# untitled.net
KiCad netlist of a schematic drawn in EAGLE
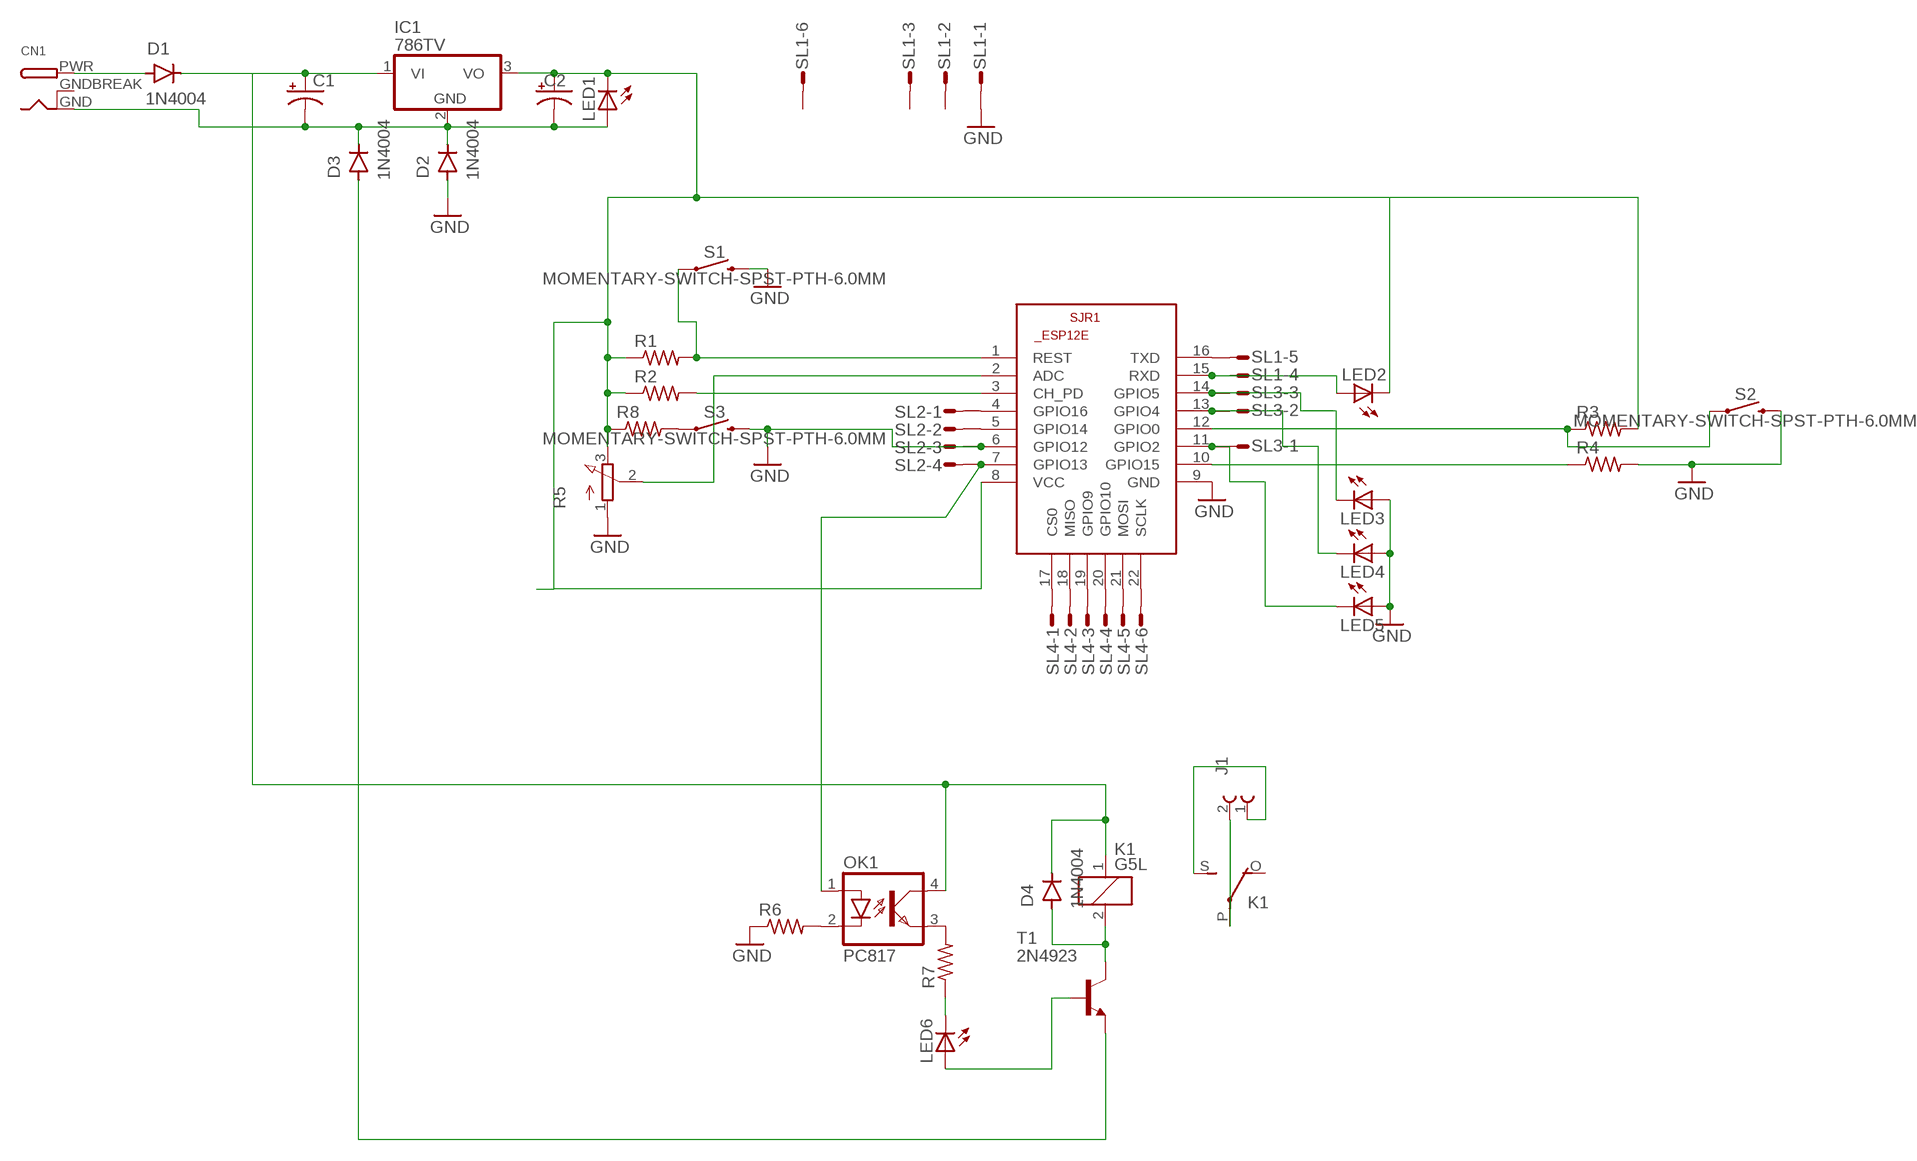
[diagram p0: schematic, sheet 1]

(export (version "E")
  (design (tool "Eeschema 10.0.6"))
  (components
    (comp (ref "C1")
      (value "CAPACITOR-PE3.5-8")
      (footprint "eagle-import:E3,5-8")
      (libsource (lib "eagle-import") (part "CAPACITOR-PE3.5-8"))
    )
    (comp (ref "C2")
      (value "CAPACITOR-PE3.5-8")
      (footprint "eagle-import:E3,5-8")
      (libsource (lib "eagle-import") (part "CAPACITOR-PE3.5-8"))
    )
    (comp (ref "CN1")
      (value "DCBARRELPTH")
      (footprint "eagle-import:DCJACK_2MM_PTH")
      (libsource (lib "eagle-import") (part "DCBARRELPTH"))
    )
    (comp (ref "D1")
      (value "1N4004")
      (footprint "eagle-import:DO-41")
      (fields
        (field (name "DIGIKEY_PART_NUMBER") "1N4004MSCT-ND")
        (field (name "MANUFACTURER") "Micro Commercial Co")
        (field (name "CREATED_BY") "PCBLayout.com")
      )
      (libsource (lib "eagle-import") (part "1N4004"))
    )
    (comp (ref "D2")
      (value "1N4004")
      (footprint "eagle-import:DO-41")
      (fields
        (field (name "DIGIKEY_PART_NUMBER") "1N4004MSCT-ND")
        (field (name "MANUFACTURER") "Micro Commercial Co")
        (field (name "CREATED_BY") "PCBLayout.com")
      )
      (libsource (lib "eagle-import") (part "1N4004"))
    )
    (comp (ref "D3")
      (value "1N4004")
      (footprint "eagle-import:DO-41")
      (fields
        (field (name "DIGIKEY_PART_NUMBER") "1N4004MSCT-ND")
        (field (name "MANUFACTURER") "Micro Commercial Co")
        (field (name "CREATED_BY") "PCBLayout.com")
      )
      (libsource (lib "eagle-import") (part "1N4004"))
    )
    (comp (ref "D4")
      (value "1N4004")
      (footprint "eagle-import:DO-41")
      (fields
        (field (name "DIGIKEY_PART_NUMBER") "1N4004MSCT-ND")
        (field (name "MANUFACTURER") "Micro Commercial Co")
        (field (name "CREATED_BY") "PCBLayout.com")
      )
      (libsource (lib "eagle-import") (part "1N4004"))
    )
    (comp (ref "IC1")
      (value "786TV")
      (footprint "eagle-import:TO220V")
      (libsource (lib "eagle-import") (part "78TV6"))
    )
    (comp (ref "J1")
      (value "691370710002B")
      (footprint "eagle-import:691370710002B")
      (libsource (lib "eagle-import") (part "691370710002B"))
    )
    (comp (ref "K1")
      (value "G5L")
      (footprint "eagle-import:G5LE")
      (libsource (lib "eagle-import") (part "G5L"))
    )
    (comp (ref "LED1")
      (value "LED5MM")
      (footprint "eagle-import:LED5MM")
      (libsource (lib "eagle-import") (part "LED5MM"))
    )
    (comp (ref "LED2")
      (value "LED5MM")
      (footprint "eagle-import:LED5MM")
      (libsource (lib "eagle-import") (part "LED5MM"))
    )
    (comp (ref "LED3")
      (value "LED5MM")
      (footprint "eagle-import:LED5MM")
      (libsource (lib "eagle-import") (part "LED5MM"))
    )
    (comp (ref "LED4")
      (value "LED5MM")
      (footprint "eagle-import:LED5MM")
      (libsource (lib "eagle-import") (part "LED5MM"))
    )
    (comp (ref "LED5")
      (value "LED5MM")
      (footprint "eagle-import:LED5MM")
      (libsource (lib "eagle-import") (part "LED5MM"))
    )
    (comp (ref "LED6")
      (value "LED5MM")
      (footprint "eagle-import:LED5MM")
      (libsource (lib "eagle-import") (part "LED5MM"))
    )
    (comp (ref "OK1")
      (value "PC817")
      (footprint "eagle-import:DIL04")
      (fields (field (name "MPN") "PC817X4J000F"))
      (libsource (lib "eagle-import") (part "PC817"))
    )
    (comp (ref "R1")
      (value "R-US_0309/10")
      (footprint "eagle-import:0309_10")
      (libsource (lib "eagle-import") (part "R-US_0309/10"))
    )
    (comp (ref "R2")
      (value "R-US_0309/10")
      (footprint "eagle-import:0309_10")
      (libsource (lib "eagle-import") (part "R-US_0309/10"))
    )
    (comp (ref "R3")
      (value "R-US_0309/10")
      (footprint "eagle-import:0309_10")
      (libsource (lib "eagle-import") (part "R-US_0309/10"))
    )
    (comp (ref "R4")
      (value "R-US_0309/10")
      (footprint "eagle-import:0309_10")
      (libsource (lib "eagle-import") (part "R-US_0309/10"))
    )
    (comp (ref "R5")
      (value "3RP/1610N")
      (footprint "eagle-import:3RP_1610N")
      (libsource (lib "eagle-import") (part "3RP/1610N"))
    )
    (comp (ref "R6")
      (value "R-US_0309/10")
      (footprint "eagle-import:0309_10")
      (libsource (lib "eagle-import") (part "R-US_0309/10"))
    )
    (comp (ref "R7")
      (value "R-US_0309/10")
      (footprint "eagle-import:0309_10")
      (libsource (lib "eagle-import") (part "R-US_0309/10"))
    )
    (comp (ref "R8")
      (value "R-US_0309/10")
      (footprint "eagle-import:0309_10")
      (libsource (lib "eagle-import") (part "R-US_0309/10"))
    )
    (comp (ref "S1")
      (value "MOMENTARY-SWITCH-SPST-PTH-6.0MM")
      (footprint "eagle-import:TACTILE_SWITCH_PTH_6.0MM")
      (libsource (lib "eagle-import") (part "MOMENTARY-SWITCH-SPST-PTH-6.0MM"))
    )
    (comp (ref "S2")
      (value "MOMENTARY-SWITCH-SPST-PTH-6.0MM")
      (footprint "eagle-import:TACTILE_SWITCH_PTH_6.0MM")
      (libsource (lib "eagle-import") (part "MOMENTARY-SWITCH-SPST-PTH-6.0MM"))
    )
    (comp (ref "S3")
      (value "MOMENTARY-SWITCH-SPST-PTH-6.0MM")
      (footprint "eagle-import:TACTILE_SWITCH_PTH_6.0MM")
      (libsource (lib "eagle-import") (part "MOMENTARY-SWITCH-SPST-PTH-6.0MM"))
    )
    (comp (ref "SJR1")
      (value "ESP8266-12EESP12E")
      (footprint "eagle-import:ESP8266-ESP12E")
      (libsource (lib "eagle-import") (part "ESP8266-12EESP12E"))
    )
    (comp (ref "SL1")
      (value "M06S")
      (footprint "eagle-import:06P")
      (libsource (lib "eagle-import") (part "M06S"))
    )
    (comp (ref "SL2")
      (value "M04S")
      (footprint "eagle-import:04P")
      (libsource (lib "eagle-import") (part "M04S"))
    )
    (comp (ref "SL3")
      (value "M03S")
      (footprint "eagle-import:03P")
      (libsource (lib "eagle-import") (part "M03S"))
    )
    (comp (ref "SL4")
      (value "M06S")
      (footprint "eagle-import:06P")
      (libsource (lib "eagle-import") (part "M06S"))
    )
    (comp (ref "T1")
      (value "2N4923")
      (footprint "eagle-import:TO126")
      (libsource (lib "eagle-import") (part "2N4923"))
    )
  )
  (nets
    (net (code "1") (name "/GNDBREAK") (class "Default")
      (node (ref "CN1") (pin "GNDBREAK") (pinfunction "GNDBREAK_GNDBREAK") (pintype "power_in"))
    )
    (net (code "2") (name "GND") (class "Default")
      (node (ref "D2") (pin "A") (pinfunction "A_A") (pintype "passive"))
      (node (ref "LED3") (pin "A") (pinfunction "A_A") (pintype "passive"))
      (node (ref "LED4") (pin "A") (pinfunction "A_A") (pintype "passive"))
      (node (ref "LED5") (pin "A") (pinfunction "A_A") (pintype "passive"))
      (node (ref "R4") (pin "2") (pinfunction "2_2") (pintype "passive"))
      (node (ref "R5") (pin "1") (pinfunction "A_1") (pintype "passive"))
      (node (ref "R6") (pin "1") (pinfunction "1_1") (pintype "passive"))
      (node (ref "S1") (pin "3") (pinfunction "2_3") (pintype "passive"))
      (node (ref "S2") (pin "3") (pinfunction "2_3") (pintype "passive"))
      (node (ref "S3") (pin "3") (pinfunction "2_3") (pintype "passive"))
      (node (ref "SJR1") (pin "6") (pinfunction "GPIO12_6") (pintype "bidirectional"))
      (node (ref "SJR1") (pin "9") (pinfunction "GND_9") (pintype "bidirectional"))
      (node (ref "SL1") (pin "1") (pinfunction "S_1") (pintype "passive"))
      (node (ref "SL2") (pin "3") (pinfunction "S_3") (pintype "passive"))
    )
    (net (code "3") (name "Net-(CN1-PadPWR)") (class "Default")
      (node (ref "CN1") (pin "PWR") (pinfunction "PWR_PWR") (pintype "power_in"))
      (node (ref "D1") (pin "A") (pinfunction "A_A") (pintype "passive"))
    )
    (net (code "4") (name "Net-(IC1-GND)") (class "Default")
      (node (ref "C1") (pin "-") (pinfunction "-_-") (pintype "passive"))
      (node (ref "C2") (pin "-") (pinfunction "-_-") (pintype "passive"))
      (node (ref "CN1") (pin "GND") (pinfunction "GND_GND") (pintype "power_in"))
      (node (ref "D2") (pin "C") (pinfunction "C_C") (pintype "passive"))
      (node (ref "D3") (pin "C") (pinfunction "C_C") (pintype "passive"))
      (node (ref "IC1") (pin "2") (pinfunction "GND_2") (pintype "passive"))
      (node (ref "LED1") (pin "A") (pinfunction "A_A") (pintype "passive"))
    )
    (net (code "5") (name "Net-(IC1-VI)") (class "Default")
      (node (ref "C1") (pin "+") (pinfunction "+_+") (pintype "passive"))
      (node (ref "D1") (pin "C") (pinfunction "C_C") (pintype "passive"))
      (node (ref "D4") (pin "C") (pinfunction "C_C") (pintype "passive"))
      (node (ref "IC1") (pin "1") (pinfunction "VI_1") (pintype "input"))
      (node (ref "K1") (pin "1") (pinfunction "1_1") (pintype "passive"))
      (node (ref "OK1") (pin "4") (pinfunction "COL_4") (pintype "passive"))
    )
    (net (code "6") (name "Net-(IC1-VO)") (class "Default")
      (node (ref "C2") (pin "+") (pinfunction "+_+") (pintype "passive"))
      (node (ref "IC1") (pin "3") (pinfunction "VO_3") (pintype "passive"))
      (node (ref "LED1") (pin "K") (pinfunction "C_K") (pintype "passive"))
      (node (ref "LED2") (pin "K") (pinfunction "C_K") (pintype "passive"))
      (node (ref "R1") (pin "1") (pinfunction "1_1") (pintype "passive"))
      (node (ref "R2") (pin "1") (pinfunction "1_1") (pintype "passive"))
      (node (ref "R3") (pin "2") (pinfunction "2_2") (pintype "passive"))
      (node (ref "R5") (pin "3") (pinfunction "E_3") (pintype "passive"))
      (node (ref "R8") (pin "1") (pinfunction "1_1") (pintype "passive"))
      (node (ref "SJR1") (pin "8") (pinfunction "VCC_8") (pintype "bidirectional"))
    )
    (net (code "7") (name "Net-(J1-1)") (class "Default")
      (node (ref "J1") (pin "2") (pinfunction "1_2") (pintype "passive"))
      (node (ref "K1") (pin "P") (pinfunction "P_P") (pintype "passive"))
    )
    (net (code "8") (name "Net-(J1-2)") (class "Default")
      (node (ref "J1") (pin "1") (pinfunction "2_1") (pintype "passive"))
      (node (ref "K1") (pin "S") (pinfunction "S_S") (pintype "passive"))
    )
    (net (code "9") (name "Net-(LED3-C)") (class "Default")
      (node (ref "LED3") (pin "K") (pinfunction "C_K") (pintype "passive"))
      (node (ref "SJR1") (pin "14") (pinfunction "GPIO5_14") (pintype "bidirectional"))
      (node (ref "SL3") (pin "3") (pinfunction "S_3") (pintype "passive"))
    )
    (net (code "10") (name "Net-(LED4-C)") (class "Default")
      (node (ref "LED4") (pin "K") (pinfunction "C_K") (pintype "passive"))
      (node (ref "SJR1") (pin "13") (pinfunction "GPIO4_13") (pintype "bidirectional"))
      (node (ref "SL3") (pin "2") (pinfunction "S_2") (pintype "passive"))
    )
    (net (code "11") (name "Net-(LED5-C)") (class "Default")
      (node (ref "LED5") (pin "K") (pinfunction "C_K") (pintype "passive"))
      (node (ref "SJR1") (pin "11") (pinfunction "GPIO2_11") (pintype "bidirectional"))
      (node (ref "SL3") (pin "1") (pinfunction "S_1") (pintype "passive"))
    )
    (net (code "12") (name "Net-(LED6-C)") (class "Default")
      (node (ref "LED6") (pin "K") (pinfunction "C_K") (pintype "passive"))
      (node (ref "R7") (pin "1") (pinfunction "1_1") (pintype "passive"))
    )
    (net (code "13") (name "Net-(OK1-A)") (class "Default")
      (node (ref "OK1") (pin "1") (pinfunction "A_1") (pintype "passive"))
      (node (ref "SJR1") (pin "7") (pinfunction "GPIO13_7") (pintype "bidirectional"))
      (node (ref "SL2") (pin "4") (pinfunction "S_4") (pintype "passive"))
    )
    (net (code "14") (name "Net-(OK1-C)") (class "Default")
      (node (ref "OK1") (pin "2") (pinfunction "C_2") (pintype "passive"))
      (node (ref "R6") (pin "2") (pinfunction "2_2") (pintype "passive"))
    )
    (net (code "15") (name "Net-(OK1-EMIT)") (class "Default")
      (node (ref "OK1") (pin "3") (pinfunction "EMIT_3") (pintype "passive"))
      (node (ref "R7") (pin "2") (pinfunction "2_2") (pintype "passive"))
    )
    (net (code "16") (name "Net-(R5-S)") (class "Default")
      (node (ref "R5") (pin "2") (pinfunction "S_2") (pintype "passive"))
      (node (ref "SJR1") (pin "2") (pinfunction "ADC_2") (pintype "bidirectional"))
    )
    (net (code "17") (name "Net-(R8-Pad2)") (class "Default")
      (node (ref "R8") (pin "2") (pinfunction "2_2") (pintype "passive"))
      (node (ref "S3") (pin "1") (pinfunction "1_1") (pintype "passive"))
    )
    (net (code "18") (name "Net-(SJR1-CH_PD)") (class "Default")
      (node (ref "R2") (pin "2") (pinfunction "2_2") (pintype "passive"))
      (node (ref "SJR1") (pin "3") (pinfunction "CH_PD_3") (pintype "bidirectional"))
    )
    (net (code "19") (name "Net-(SJR1-CS0)") (class "Default")
      (node (ref "SJR1") (pin "17") (pinfunction "CS0_17") (pintype "bidirectional"))
      (node (ref "SL4") (pin "1") (pinfunction "S_1") (pintype "passive"))
    )
    (net (code "20") (name "Net-(SJR1-GPIO0)") (class "Default")
      (node (ref "R3") (pin "1") (pinfunction "1_1") (pintype "passive"))
      (node (ref "S2") (pin "1") (pinfunction "1_1") (pintype "passive"))
      (node (ref "SJR1") (pin "12") (pinfunction "GPIO0_12") (pintype "bidirectional"))
    )
    (net (code "21") (name "Net-(SJR1-GPIO9)") (class "Default")
      (node (ref "SJR1") (pin "19") (pinfunction "GPIO9_19") (pintype "bidirectional"))
      (node (ref "SL4") (pin "3") (pinfunction "S_3") (pintype "passive"))
    )
    (net (code "22") (name "Net-(SJR1-GPIO10)") (class "Default")
      (node (ref "SJR1") (pin "20") (pinfunction "GPIO10_20") (pintype "bidirectional"))
      (node (ref "SL4") (pin "4") (pinfunction "S_4") (pintype "passive"))
    )
    (net (code "23") (name "Net-(SJR1-GPIO14)") (class "Default")
      (node (ref "SJR1") (pin "5") (pinfunction "GPIO14_5") (pintype "bidirectional"))
      (node (ref "SL2") (pin "2") (pinfunction "S_2") (pintype "passive"))
    )
    (net (code "24") (name "Net-(SJR1-GPIO15)") (class "Default")
      (node (ref "R4") (pin "1") (pinfunction "1_1") (pintype "passive"))
      (node (ref "SJR1") (pin "10") (pinfunction "GPIO15_10") (pintype "bidirectional"))
    )
    (net (code "25") (name "Net-(SJR1-GPIO16)") (class "Default")
      (node (ref "SJR1") (pin "4") (pinfunction "GPIO16_4") (pintype "bidirectional"))
      (node (ref "SL2") (pin "1") (pinfunction "S_1") (pintype "passive"))
    )
    (net (code "26") (name "Net-(SJR1-MISO)") (class "Default")
      (node (ref "SJR1") (pin "18") (pinfunction "MISO_18") (pintype "bidirectional"))
      (node (ref "SL4") (pin "2") (pinfunction "S_2") (pintype "passive"))
    )
    (net (code "27") (name "Net-(SJR1-MOSI)") (class "Default")
      (node (ref "SJR1") (pin "21") (pinfunction "MOSI_21") (pintype "bidirectional"))
      (node (ref "SL4") (pin "5") (pinfunction "S_5") (pintype "passive"))
    )
    (net (code "28") (name "Net-(SJR1-REST)") (class "Default")
      (node (ref "R1") (pin "2") (pinfunction "2_2") (pintype "passive"))
      (node (ref "S1") (pin "1") (pinfunction "1_1") (pintype "passive"))
      (node (ref "SJR1") (pin "1") (pinfunction "REST_1") (pintype "bidirectional"))
    )
    (net (code "29") (name "Net-(SJR1-RXD)") (class "Default")
      (node (ref "LED2") (pin "A") (pinfunction "A_A") (pintype "passive"))
      (node (ref "SJR1") (pin "15") (pinfunction "RXD_15") (pintype "bidirectional"))
      (node (ref "SL1") (pin "4") (pinfunction "S_4") (pintype "passive"))
    )
    (net (code "30") (name "Net-(SJR1-SCLK)") (class "Default")
      (node (ref "SJR1") (pin "22") (pinfunction "SCLK_22") (pintype "bidirectional"))
      (node (ref "SL4") (pin "6") (pinfunction "S_6") (pintype "passive"))
    )
    (net (code "31") (name "Net-(SJR1-TXD)") (class "Default")
      (node (ref "SJR1") (pin "16") (pinfunction "TXD_16") (pintype "bidirectional"))
      (node (ref "SL1") (pin "5") (pinfunction "S_5") (pintype "passive"))
    )
    (net (code "32") (name "Net-(T1-B)") (class "Default")
      (node (ref "LED6") (pin "A") (pinfunction "A_A") (pintype "passive"))
      (node (ref "T1") (pin "3") (pinfunction "B_3") (pintype "passive"))
    )
    (net (code "33") (name "Net-(T1-C)") (class "Default")
      (node (ref "D4") (pin "A") (pinfunction "A_A") (pintype "passive"))
      (node (ref "K1") (pin "2") (pinfunction "2_2") (pintype "passive"))
      (node (ref "T1") (pin "2") (pinfunction "C_2") (pintype "passive"))
    )
    (net (code "34") (name "Net-(T1-E)") (class "Default")
      (node (ref "D3") (pin "A") (pinfunction "A_A") (pintype "passive"))
      (node (ref "T1") (pin "1") (pinfunction "E_1") (pintype "passive"))
    )
    (net (code "35") (name "unconnected-(K1-PadO)") (class "Default")
      (node (ref "K1") (pin "O") (pinfunction "O_O") (pintype "passive"))
    )
    (net (code "36") (name "unconnected-(SL1B-S-Pad2)") (class "Default")
      (node (ref "SL1") (pin "2") (pinfunction "S_2") (pintype "passive"))
    )
    (net (code "37") (name "unconnected-(SL1C-S-Pad3)") (class "Default")
      (node (ref "SL1") (pin "3") (pinfunction "S_3") (pintype "passive"))
    )
    (net (code "38") (name "unconnected-(SL1F-S-Pad6)") (class "Default")
      (node (ref "SL1") (pin "6") (pinfunction "S_6") (pintype "passive"))
    )
  )
)
